# Pololu_Magnetic_Encoder_AS5035.net
KiCad netlist of a schematic drawn in EAGLE
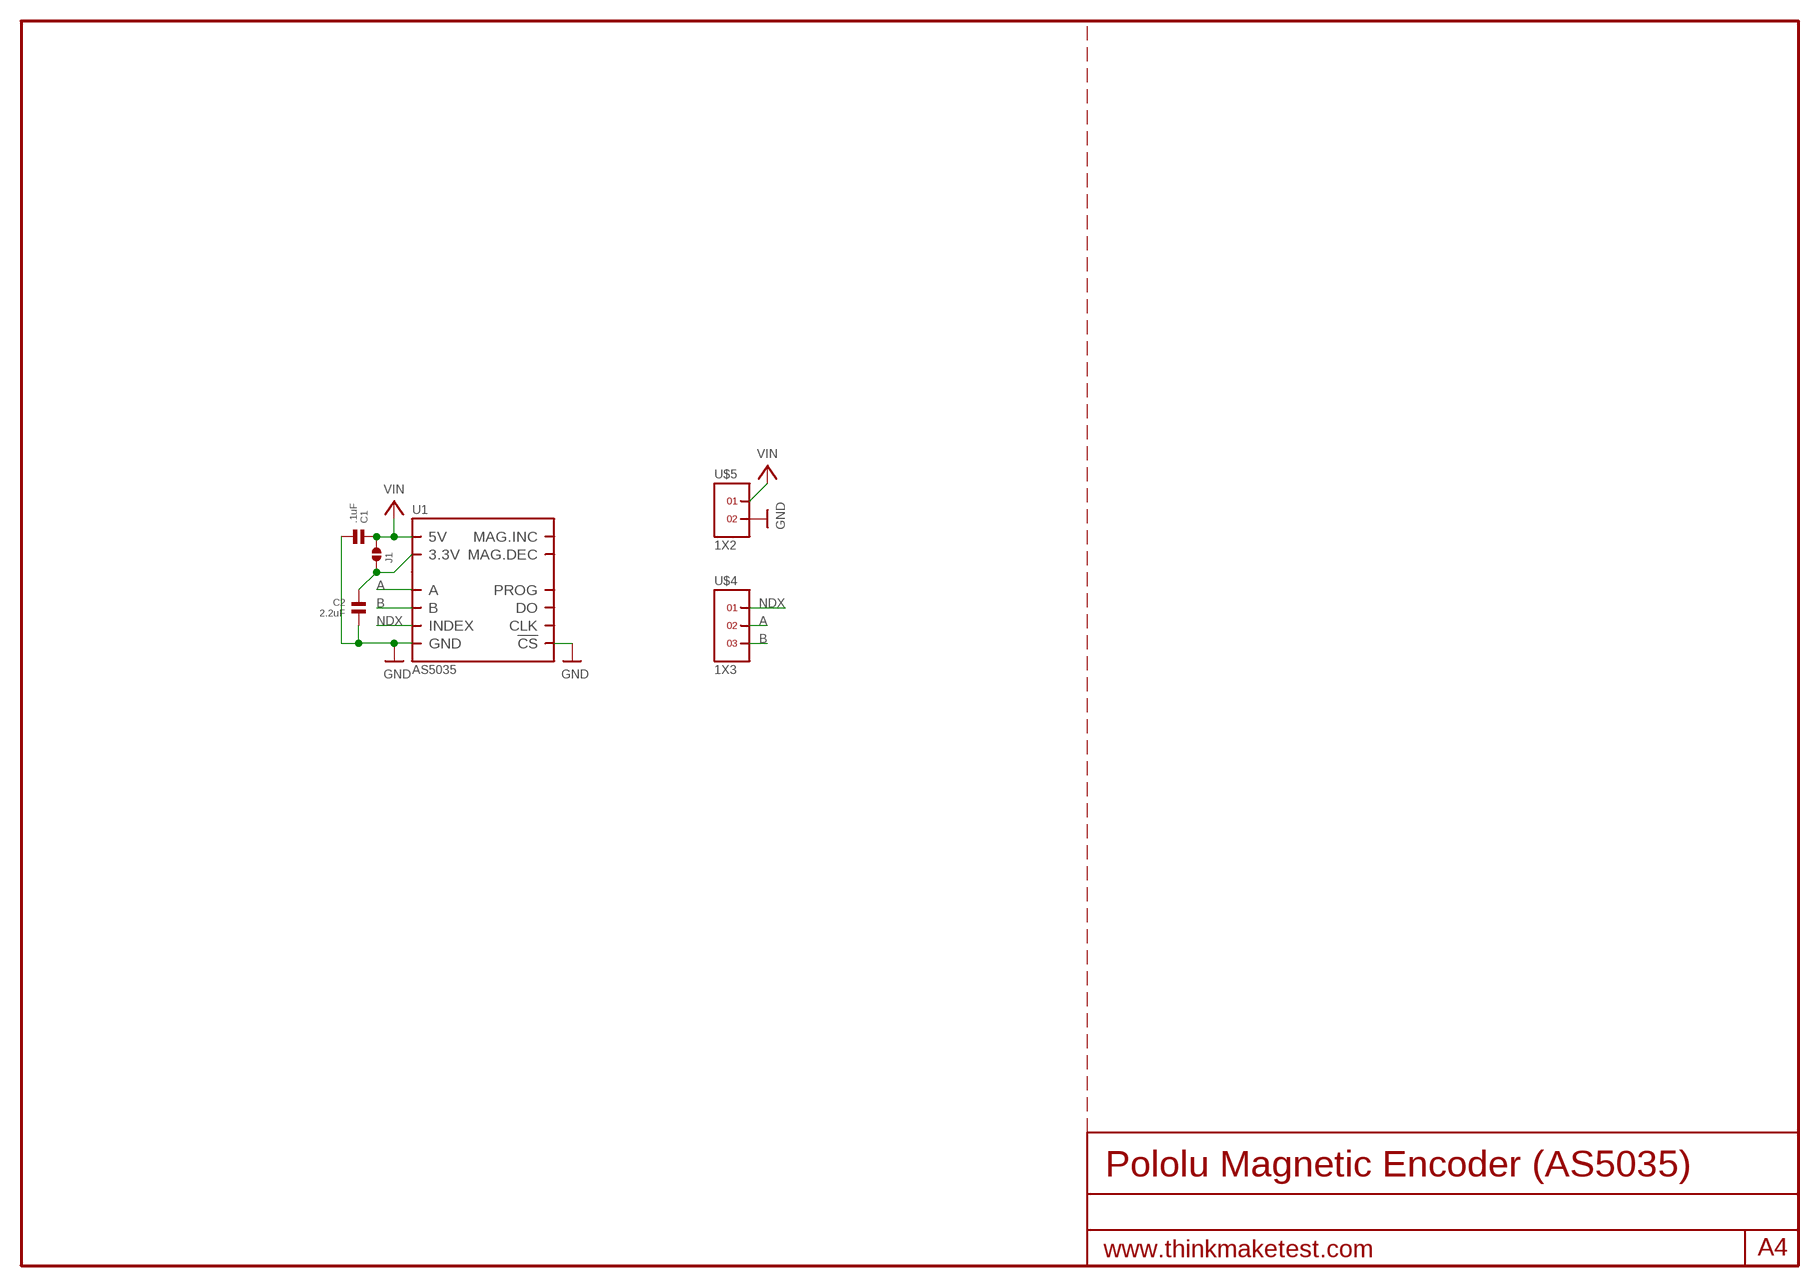
[diagram p0: schematic, sheet 1]

(export (version "E")
  (design (tool "Eeschema 10.0.6"))
  (components
    (comp (ref "C1")
      (value ".1uF")
      (footprint "eagle-import:0603")
      (libsource (lib "eagle-import") (part "CAPACITOR.0603"))
    )
    (comp (ref "C2")
      (value "2.2uF")
      (footprint "eagle-import:0603")
      (libsource (lib "eagle-import") (part "CAPACITOR.0603"))
    )
    (comp (ref "J1")
      (value "SOLDERJUMPER.2.LRG.PASTE")
      (footprint "eagle-import:2.LRG.PASTE")
      (libsource (lib "eagle-import") (part "SOLDERJUMPER.2.LRG.PASTE"))
    )
    (comp (ref "U$4")
      (value "1X3")
      (footprint "eagle-import:1X3")
      (libsource (lib "eagle-import") (part "1X3"))
    )
    (comp (ref "U$5")
      (value "1X2")
      (footprint "eagle-import:1X2")
      (libsource (lib "eagle-import") (part "1X2"))
    )
    (comp (ref "U1")
      (value "AS5035")
      (footprint "eagle-import:SSOP16")
      (libsource (lib "eagle-import") (part "AS5035"))
    )
  )
  (nets
    (net (code "1") (name "/A") (class "Default")
      (node (ref "U$4") (pin "2") (pinfunction "2_2") (pintype "bidirectional"))
      (node (ref "U1") (pin "3") (pinfunction "A_3") (pintype "bidirectional"))
    )
    (net (code "2") (name "/B") (class "Default")
      (node (ref "U$4") (pin "3") (pinfunction "3_3") (pintype "bidirectional"))
      (node (ref "U1") (pin "4") (pinfunction "B_4") (pintype "bidirectional"))
    )
    (net (code "3") (name "/NDX") (class "Default")
      (node (ref "U$4") (pin "1") (pinfunction "1_1") (pintype "bidirectional"))
      (node (ref "U1") (pin "6") (pinfunction "INDEX_6") (pintype "bidirectional"))
    )
    (net (code "4") (name "GND") (class "Default")
      (node (ref "C1") (pin "2") (pinfunction "2_2") (pintype "bidirectional"))
      (node (ref "C2") (pin "2") (pinfunction "2_2") (pintype "bidirectional"))
      (node (ref "U$5") (pin "2") (pinfunction "2_2") (pintype "bidirectional"))
      (node (ref "U1") (pin "11") (pinfunction "~{CS}_11") (pintype "bidirectional"))
      (node (ref "U1") (pin "7") (pinfunction "GND_7") (pintype "bidirectional"))
    )
    (net (code "5") (name "Net-(U1-3.3V)") (class "Default")
      (node (ref "C2") (pin "1") (pinfunction "1_1") (pintype "bidirectional"))
      (node (ref "J1") (pin "1") (pinfunction "1_1") (pintype "bidirectional"))
      (node (ref "U1") (pin "15") (pinfunction "3.3V_15") (pintype "bidirectional"))
    )
    (net (code "6") (name "VIN") (class "Default")
      (node (ref "C1") (pin "1") (pinfunction "1_1") (pintype "bidirectional"))
      (node (ref "J1") (pin "2") (pinfunction "2_2") (pintype "bidirectional"))
      (node (ref "U$5") (pin "1") (pinfunction "1_1") (pintype "bidirectional"))
      (node (ref "U1") (pin "16") (pinfunction "5V_16") (pintype "bidirectional"))
    )
    (net (code "7") (name "unconnected-(U1-CLK-Pad10)") (class "Default")
      (node (ref "U1") (pin "10") (pinfunction "CLK_10") (pintype "bidirectional"))
    )
    (net (code "8") (name "unconnected-(U1-DO-Pad9)") (class "Default")
      (node (ref "U1") (pin "9") (pinfunction "DO_9") (pintype "bidirectional"))
    )
    (net (code "9") (name "unconnected-(U1-MAG.DEC-Pad2)") (class "Default")
      (node (ref "U1") (pin "2") (pinfunction "MAG.DEC_2") (pintype "bidirectional"))
    )
    (net (code "10") (name "unconnected-(U1-MAG.INC-Pad1)") (class "Default")
      (node (ref "U1") (pin "1") (pinfunction "MAG.INC_1") (pintype "bidirectional"))
    )
    (net (code "11") (name "unconnected-(U1-PROG-Pad8)") (class "Default")
      (node (ref "U1") (pin "8") (pinfunction "PROG_8") (pintype "bidirectional"))
    )
  )
)
